# P_ytka.net
KiCad netlist of a schematic drawn in EAGLE
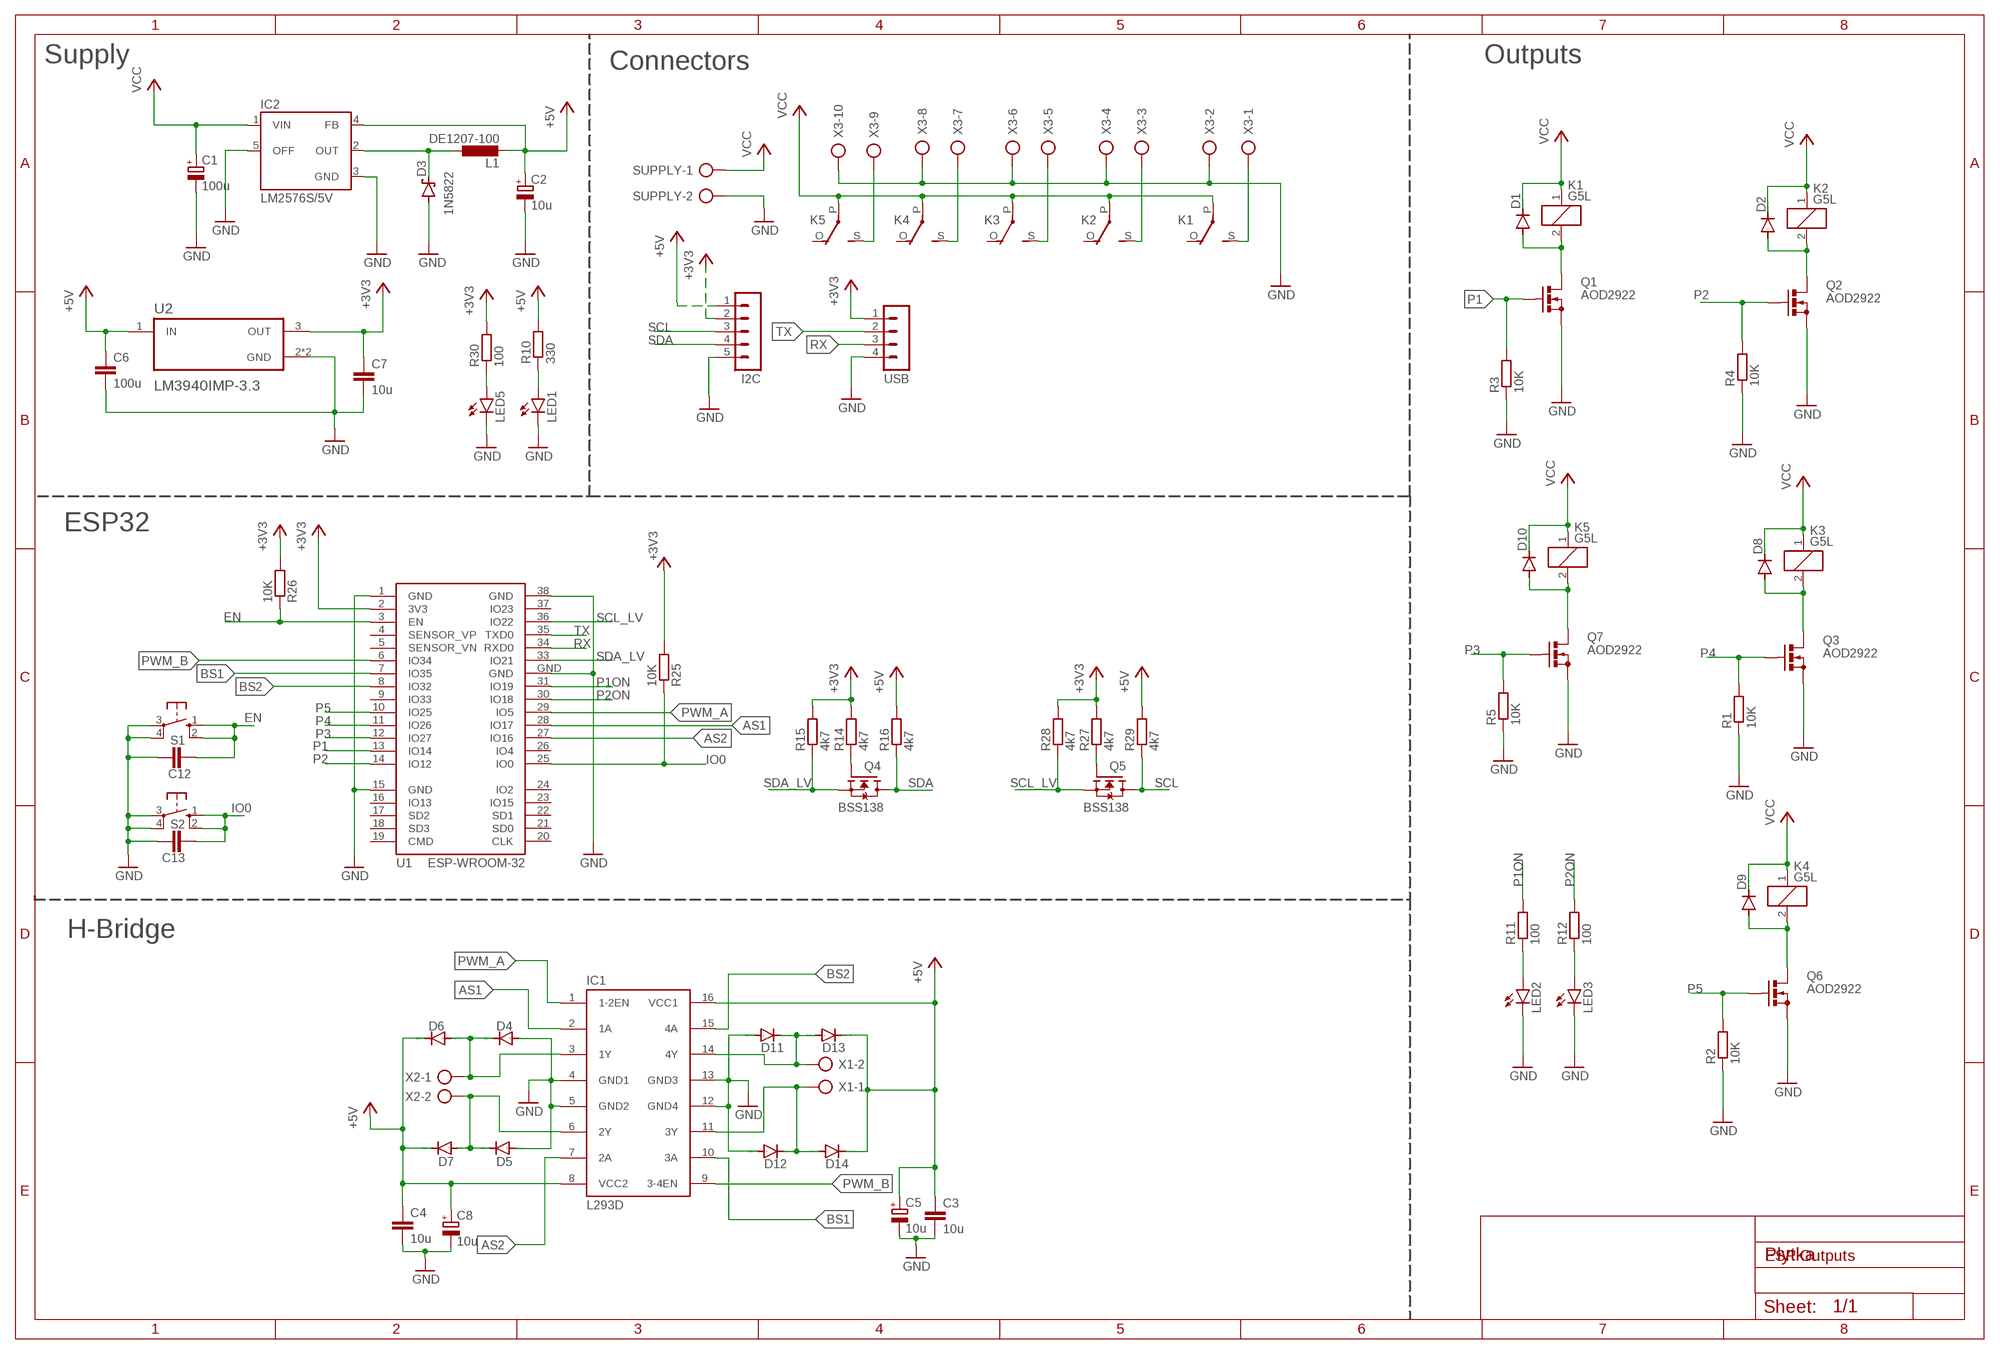
[diagram p0: schematic, sheet 1]

(export (version "E")
  (design (tool "Eeschema 10.0.6"))
  (components
    (comp (ref "C1")
      (value "100u")
      (footprint "eagle-import:E2,5-6")
      (libsource (lib "eagle-import") (part "CPOL-EUE2.5-6"))
    )
    (comp (ref "C2")
      (value "10u")
      (footprint "eagle-import:E3,5-8")
      (libsource (lib "eagle-import") (part "CPOL-EUE3.5-8"))
    )
    (comp (ref "C3")
      (value "10u")
      (footprint "eagle-import:C0805K")
      (libsource (lib "eagle-import") (part "resistor_348_C-EUC0805K"))
    )
    (comp (ref "C4")
      (value "10u")
      (footprint "eagle-import:C0805K")
      (libsource (lib "eagle-import") (part "resistor_348_C-EUC0805K"))
    )
    (comp (ref "C5")
      (value "10u")
      (footprint "eagle-import:E5-8,5")
      (libsource (lib "eagle-import") (part "resistor_348_CPOL-EUE5-8.5"))
    )
    (comp (ref "C6")
      (value "100u")
      (footprint "eagle-import:C0805K")
      (libsource (lib "eagle-import") (part "C-EUC0805K"))
    )
    (comp (ref "C7")
      (value "10u")
      (footprint "eagle-import:C0805K")
      (libsource (lib "eagle-import") (part "C-EUC0805K"))
    )
    (comp (ref "C8")
      (value "10u")
      (footprint "eagle-import:E5-8,5")
      (libsource (lib "eagle-import") (part "resistor_348_CPOL-EUE5-8.5"))
    )
    (comp (ref "C12")
      (value "C-EUC0805K")
      (footprint "eagle-import:C0805K")
      (libsource (lib "eagle-import") (part "C-EUC0805K"))
    )
    (comp (ref "C13")
      (value "C-EUC0805K")
      (footprint "eagle-import:C0805K")
      (libsource (lib "eagle-import") (part "C-EUC0805K"))
    )
    (comp (ref "D1")
      (value "DIODE-DO214AC")
      (footprint "eagle-import:DO214AC")
      (libsource (lib "eagle-import") (part "DIODE-DO214AC"))
    )
    (comp (ref "D2")
      (value "DIODE-DO214AC")
      (footprint "eagle-import:DO214AC")
      (libsource (lib "eagle-import") (part "DIODE-DO214AC"))
    )
    (comp (ref "D3")
      (value "1N5822")
      (footprint "eagle-import:C4111-15")
      (libsource (lib "eagle-import") (part "1N5908"))
    )
    (comp (ref "D4")
      (value "DIODE-DO214AC")
      (footprint "eagle-import:DO214AC")
      (libsource (lib "eagle-import") (part "DIODE-DO214AC"))
    )
    (comp (ref "D5")
      (value "DIODE-DO214AC")
      (footprint "eagle-import:DO214AC")
      (libsource (lib "eagle-import") (part "DIODE-DO214AC"))
    )
    (comp (ref "D6")
      (value "DIODE-DO214AC")
      (footprint "eagle-import:DO214AC")
      (libsource (lib "eagle-import") (part "DIODE-DO214AC"))
    )
    (comp (ref "D7")
      (value "DIODE-DO214AC")
      (footprint "eagle-import:DO214AC")
      (libsource (lib "eagle-import") (part "DIODE-DO214AC"))
    )
    (comp (ref "D8")
      (value "DIODE-DO214AC")
      (footprint "eagle-import:DO214AC")
      (libsource (lib "eagle-import") (part "DIODE-DO214AC"))
    )
    (comp (ref "D9")
      (value "DIODE-DO214AC")
      (footprint "eagle-import:DO214AC")
      (libsource (lib "eagle-import") (part "DIODE-DO214AC"))
    )
    (comp (ref "D10")
      (value "DIODE-DO214AC")
      (footprint "eagle-import:DO214AC")
      (libsource (lib "eagle-import") (part "DIODE-DO214AC"))
    )
    (comp (ref "D11")
      (value "DIODE-DO214AC")
      (footprint "eagle-import:DO214AC")
      (libsource (lib "eagle-import") (part "DIODE-DO214AC"))
    )
    (comp (ref "D12")
      (value "DIODE-DO214AC")
      (footprint "eagle-import:DO214AC")
      (libsource (lib "eagle-import") (part "DIODE-DO214AC"))
    )
    (comp (ref "D13")
      (value "DIODE-DO214AC")
      (footprint "eagle-import:DO214AC")
      (libsource (lib "eagle-import") (part "DIODE-DO214AC"))
    )
    (comp (ref "D14")
      (value "DIODE-DO214AC")
      (footprint "eagle-import:DO214AC")
      (libsource (lib "eagle-import") (part "DIODE-DO214AC"))
    )
    (comp (ref "I2C")
      (value "MA05-1")
      (footprint "eagle-import:MA05-1")
      (libsource (lib "eagle-import") (part "MA05-1"))
    )
    (comp (ref "IC1")
      (value "L293D")
      (footprint "eagle-import:DIL16")
      (libsource (lib "eagle-import") (part "L293D"))
    )
    (comp (ref "IC2")
      (value "LM2576S/5V")
      (footprint "eagle-import:TO220-5")
      (libsource (lib "eagle-import") (part "LM2576T"))
    )
    (comp (ref "K1")
      (value "G5L")
      (footprint "eagle-import:G5LE")
      (libsource (lib "eagle-import") (part "G5L"))
    )
    (comp (ref "K2")
      (value "G5L")
      (footprint "eagle-import:G5LE")
      (libsource (lib "eagle-import") (part "G5L"))
    )
    (comp (ref "K3")
      (value "G5L")
      (footprint "eagle-import:G5LE")
      (libsource (lib "eagle-import") (part "G5L"))
    )
    (comp (ref "K4")
      (value "G5L")
      (footprint "eagle-import:G5LE")
      (libsource (lib "eagle-import") (part "G5L"))
    )
    (comp (ref "K5")
      (value "G5L")
      (footprint "eagle-import:G5LE")
      (libsource (lib "eagle-import") (part "G5L"))
    )
    (comp (ref "L1")
      (value "DE1207-100")
      (footprint "eagle-import:DE1207")
      (libsource (lib "eagle-import") (part "DE1207-100"))
    )
    (comp (ref "LED1")
      (value "LEDSML0805")
      (footprint "eagle-import:SML0805")
      (libsource (lib "eagle-import") (part "LEDSML0805"))
    )
    (comp (ref "LED2")
      (value "LEDSML0805")
      (footprint "eagle-import:SML0805")
      (libsource (lib "eagle-import") (part "LEDSML0805"))
    )
    (comp (ref "LED3")
      (value "LEDSML0805")
      (footprint "eagle-import:SML0805")
      (libsource (lib "eagle-import") (part "LEDSML0805"))
    )
    (comp (ref "LED5")
      (value "LEDSML0805")
      (footprint "eagle-import:SML0805")
      (libsource (lib "eagle-import") (part "LEDSML0805"))
    )
    (comp (ref "Q1")
      (value "AOD2922")
      (footprint "eagle-import:TO252AA")
      (libsource (lib "eagle-import") (part "MOSFET_NIXTY8N65X2"))
    )
    (comp (ref "Q2")
      (value "AOD2922")
      (footprint "eagle-import:TO252AA")
      (libsource (lib "eagle-import") (part "MOSFET_NIXTY8N65X2"))
    )
    (comp (ref "Q3")
      (value "AOD2922")
      (footprint "eagle-import:TO252AA")
      (libsource (lib "eagle-import") (part "MOSFET_NIXTY8N65X2"))
    )
    (comp (ref "Q4")
      (value "BSS138")
      (footprint "eagle-import:SOT23")
      (fields (field (name "MF") "Fairchild"))
      (libsource (lib "eagle-import") (part "BSS138"))
    )
    (comp (ref "Q5")
      (value "BSS138")
      (footprint "eagle-import:SOT23")
      (fields (field (name "MF") "Fairchild"))
      (libsource (lib "eagle-import") (part "BSS138"))
    )
    (comp (ref "Q6")
      (value "AOD2922")
      (footprint "eagle-import:TO252AA")
      (libsource (lib "eagle-import") (part "MOSFET_NIXTY8N65X2"))
    )
    (comp (ref "Q7")
      (value "AOD2922")
      (footprint "eagle-import:TO252AA")
      (libsource (lib "eagle-import") (part "MOSFET_NIXTY8N65X2"))
    )
    (comp (ref "R1")
      (value "10K")
      (footprint "eagle-import:R0805")
      (libsource (lib "eagle-import") (part "R-EU_R0805"))
    )
    (comp (ref "R2")
      (value "10K")
      (footprint "eagle-import:R0805")
      (libsource (lib "eagle-import") (part "R-EU_R0805"))
    )
    (comp (ref "R3")
      (value "10K")
      (footprint "eagle-import:R0805")
      (libsource (lib "eagle-import") (part "R-EU_R0805"))
    )
    (comp (ref "R4")
      (value "10K")
      (footprint "eagle-import:R0805")
      (libsource (lib "eagle-import") (part "R-EU_R0805"))
    )
    (comp (ref "R5")
      (value "10K")
      (footprint "eagle-import:R0805")
      (libsource (lib "eagle-import") (part "R-EU_R0805"))
    )
    (comp (ref "R10")
      (value "330")
      (footprint "eagle-import:R0805")
      (libsource (lib "eagle-import") (part "R-EU_R0805"))
    )
    (comp (ref "R11")
      (value "100")
      (footprint "eagle-import:R0805")
      (libsource (lib "eagle-import") (part "R-EU_R0805"))
    )
    (comp (ref "R12")
      (value "100")
      (footprint "eagle-import:R0805")
      (libsource (lib "eagle-import") (part "R-EU_R0805"))
    )
    (comp (ref "R14")
      (value "4k7")
      (footprint "eagle-import:R0805")
      (libsource (lib "eagle-import") (part "R-EU_R0805"))
    )
    (comp (ref "R15")
      (value "4k7")
      (footprint "eagle-import:R0805")
      (libsource (lib "eagle-import") (part "R-EU_R0805"))
    )
    (comp (ref "R16")
      (value "4k7")
      (footprint "eagle-import:R0805")
      (libsource (lib "eagle-import") (part "R-EU_R0805"))
    )
    (comp (ref "R25")
      (value "10K")
      (footprint "eagle-import:R0805")
      (libsource (lib "eagle-import") (part "R-EU_R0805"))
    )
    (comp (ref "R26")
      (value "10K")
      (footprint "eagle-import:R0805")
      (libsource (lib "eagle-import") (part "R-EU_R0805"))
    )
    (comp (ref "R27")
      (value "4k7")
      (footprint "eagle-import:R0805")
      (libsource (lib "eagle-import") (part "R-EU_R0805"))
    )
    (comp (ref "R28")
      (value "4k7")
      (footprint "eagle-import:R0805")
      (libsource (lib "eagle-import") (part "R-EU_R0805"))
    )
    (comp (ref "R29")
      (value "4k7")
      (footprint "eagle-import:R0805")
      (libsource (lib "eagle-import") (part "R-EU_R0805"))
    )
    (comp (ref "R30")
      (value "100")
      (footprint "eagle-import:R0805")
      (libsource (lib "eagle-import") (part "R-EU_R0805"))
    )
    (comp (ref "S1")
      (value "10-XX")
      (footprint "eagle-import:B3F-10XX")
      (fields (field (name "MPN") "B3F-1000"))
      (libsource (lib "eagle-import") (part "10-XX"))
    )
    (comp (ref "S2")
      (value "10-XX")
      (footprint "eagle-import:B3F-10XX")
      (fields (field (name "MPN") "B3F-1000"))
      (libsource (lib "eagle-import") (part "10-XX"))
    )
    (comp (ref "SUPPLY")
      (value "AK500/2-H")
      (footprint "eagle-import:AK500_2-H")
      (libsource (lib "eagle-import") (part "AK500/2-H"))
    )
    (comp (ref "U1")
      (value "ESP-WROOM-32")
      (footprint "eagle-import:ESP-WROOM-32")
      (libsource (lib "eagle-import") (part "ESP-WROOM-32"))
    )
    (comp (ref "U2")
      (value "LM3940IMP-3.3")
      (footprint "eagle-import:SOT230P700X180-4N")
      (fields (field (name "MF") "Texas Instruments"))
      (libsource (lib "eagle-import") (part "LM3940IMP-3.3"))
    )
    (comp (ref "USB")
      (value "MA04-1")
      (footprint "eagle-import:MA04-1")
      (libsource (lib "eagle-import") (part "MA04-1"))
    )
    (comp (ref "X1")
      (value "AK500/2")
      (footprint "eagle-import:AK500_2")
      (libsource (lib "eagle-import") (part "AK500/2"))
    )
    (comp (ref "X2")
      (value "AK500/2")
      (footprint "eagle-import:AK500_2")
      (libsource (lib "eagle-import") (part "AK500/2"))
    )
    (comp (ref "X3")
      (value "AK500/10")
      (footprint "eagle-import:AK500_10")
      (libsource (lib "eagle-import") (part "AK500/10"))
    )
  )
  (nets
    (net (code "1") (name "+3V3") (class "Default")
      (node (ref "C7") (pin "1") (pinfunction "1_1") (pintype "passive"))
      (node (ref "I2C") (pin "2") (pinfunction "2_2") (pintype "passive"))
      (node (ref "R14") (pin "2") (pinfunction "2_2") (pintype "passive"))
      (node (ref "R15") (pin "2") (pinfunction "2_2") (pintype "passive"))
      (node (ref "R25") (pin "2") (pinfunction "2_2") (pintype "passive"))
      (node (ref "R26") (pin "2") (pinfunction "2_2") (pintype "passive"))
      (node (ref "R27") (pin "2") (pinfunction "2_2") (pintype "passive"))
      (node (ref "R28") (pin "2") (pinfunction "2_2") (pintype "passive"))
      (node (ref "R30") (pin "2") (pinfunction "2_2") (pintype "passive"))
      (node (ref "U1") (pin "2") (pinfunction "3V3_2") (pintype "power_in"))
      (node (ref "U2") (pin "3") (pinfunction "OUT_3") (pintype "output"))
      (node (ref "USB") (pin "1") (pinfunction "1_1") (pintype "passive"))
    )
    (net (code "2") (name "+5V") (class "Default")
      (node (ref "C2") (pin "+") (pinfunction "+_+") (pintype "passive"))
      (node (ref "C3") (pin "1") (pinfunction "1_1") (pintype "passive"))
      (node (ref "C4") (pin "1") (pinfunction "1_1") (pintype "passive"))
      (node (ref "C5") (pin "+") (pinfunction "+_+") (pintype "passive"))
      (node (ref "C6") (pin "1") (pinfunction "1_1") (pintype "passive"))
      (node (ref "C8") (pin "+") (pinfunction "+_+") (pintype "passive"))
      (node (ref "D13") (pin "C") (pinfunction "C_C") (pintype "passive"))
      (node (ref "D14") (pin "C") (pinfunction "C_C") (pintype "passive"))
      (node (ref "D6") (pin "C") (pinfunction "C_C") (pintype "passive"))
      (node (ref "D7") (pin "C") (pinfunction "C_C") (pintype "passive"))
      (node (ref "I2C") (pin "1") (pinfunction "1_1") (pintype "passive"))
      (node (ref "IC1") (pin "16") (pinfunction "VCC1_16") (pintype "power_in"))
      (node (ref "IC1") (pin "8") (pinfunction "VCC2_8") (pintype "power_in"))
      (node (ref "IC2") (pin "4") (pinfunction "FB_4") (pintype "input"))
      (node (ref "L1") (pin "2") (pinfunction "2_2") (pintype "passive"))
      (node (ref "R10") (pin "2") (pinfunction "2_2") (pintype "passive"))
      (node (ref "R16") (pin "2") (pinfunction "2_2") (pintype "passive"))
      (node (ref "R29") (pin "2") (pinfunction "2_2") (pintype "passive"))
      (node (ref "U2") (pin "1") (pinfunction "IN_1") (pintype "input"))
    )
    (net (code "3") (name "/EN") (class "Default")
      (node (ref "C12") (pin "2") (pinfunction "2_2") (pintype "passive"))
      (node (ref "R26") (pin "1") (pinfunction "1_1") (pintype "passive"))
      (node (ref "S1") (pin "1") (pinfunction "S_1") (pintype "passive"))
      (node (ref "S1") (pin "2") (pinfunction "S1_2") (pintype "passive"))
      (node (ref "U1") (pin "3") (pinfunction "EN_3") (pintype "input"))
    )
    (net (code "4") (name "/IO0") (class "Default")
      (node (ref "C13") (pin "2") (pinfunction "2_2") (pintype "passive"))
      (node (ref "R25") (pin "1") (pinfunction "1_1") (pintype "passive"))
      (node (ref "S2") (pin "1") (pinfunction "S_1") (pintype "passive"))
      (node (ref "S2") (pin "2") (pinfunction "S1_2") (pintype "passive"))
      (node (ref "U1") (pin "25") (pinfunction "IO0_25") (pintype "bidirectional"))
    )
    (net (code "5") (name "/P1ON") (class "Default")
      (node (ref "R11") (pin "2") (pinfunction "2_2") (pintype "passive"))
      (node (ref "U1") (pin "31") (pinfunction "IO19_31") (pintype "bidirectional"))
    )
    (net (code "6") (name "/P2") (class "Default")
      (node (ref "Q2") (pin "1") (pinfunction "G_1") (pintype "passive"))
      (node (ref "R4") (pin "2") (pinfunction "2_2") (pintype "passive"))
      (node (ref "U1") (pin "14") (pinfunction "IO12_14") (pintype "bidirectional"))
    )
    (net (code "7") (name "/P2ON") (class "Default")
      (node (ref "R12") (pin "2") (pinfunction "2_2") (pintype "passive"))
      (node (ref "U1") (pin "30") (pinfunction "IO18_30") (pintype "bidirectional"))
    )
    (net (code "8") (name "/P3") (class "Default")
      (node (ref "Q7") (pin "1") (pinfunction "G_1") (pintype "passive"))
      (node (ref "R5") (pin "2") (pinfunction "2_2") (pintype "passive"))
      (node (ref "U1") (pin "12") (pinfunction "IO27_12") (pintype "bidirectional"))
    )
    (net (code "9") (name "/P4") (class "Default")
      (node (ref "Q3") (pin "1") (pinfunction "G_1") (pintype "passive"))
      (node (ref "R1") (pin "2") (pinfunction "2_2") (pintype "passive"))
      (node (ref "U1") (pin "11") (pinfunction "IO26_11") (pintype "bidirectional"))
    )
    (net (code "10") (name "/P5") (class "Default")
      (node (ref "Q6") (pin "1") (pinfunction "G_1") (pintype "passive"))
      (node (ref "R2") (pin "2") (pinfunction "2_2") (pintype "passive"))
      (node (ref "U1") (pin "10") (pinfunction "IO25_10") (pintype "bidirectional"))
    )
    (net (code "11") (name "/SCL") (class "Default")
      (node (ref "I2C") (pin "3") (pinfunction "3_3") (pintype "passive"))
      (node (ref "Q5") (pin "3") (pinfunction "D_3") (pintype "passive"))
      (node (ref "R29") (pin "1") (pinfunction "1_1") (pintype "passive"))
    )
    (net (code "12") (name "/SCL_LV") (class "Default")
      (node (ref "Q5") (pin "2") (pinfunction "S_2") (pintype "passive"))
      (node (ref "R28") (pin "1") (pinfunction "1_1") (pintype "passive"))
      (node (ref "U1") (pin "36") (pinfunction "IO22_36") (pintype "bidirectional"))
    )
    (net (code "13") (name "/SDA") (class "Default")
      (node (ref "I2C") (pin "4") (pinfunction "4_4") (pintype "passive"))
      (node (ref "Q4") (pin "3") (pinfunction "D_3") (pintype "passive"))
      (node (ref "R16") (pin "1") (pinfunction "1_1") (pintype "passive"))
    )
    (net (code "14") (name "/SDA_LV") (class "Default")
      (node (ref "Q4") (pin "2") (pinfunction "S_2") (pintype "passive"))
      (node (ref "R15") (pin "1") (pinfunction "1_1") (pintype "passive"))
      (node (ref "U1") (pin "33") (pinfunction "IO21_33") (pintype "bidirectional"))
    )
    (net (code "15") (name "AS1") (class "Default")
      (node (ref "IC1") (pin "2") (pinfunction "1A_2") (pintype "input"))
      (node (ref "U1") (pin "28") (pinfunction "IO17_28") (pintype "bidirectional"))
    )
    (net (code "16") (name "AS2") (class "Default")
      (node (ref "IC1") (pin "7") (pinfunction "2A_7") (pintype "input"))
      (node (ref "U1") (pin "27") (pinfunction "IO16_27") (pintype "bidirectional"))
    )
    (net (code "17") (name "BS1") (class "Default")
      (node (ref "IC1") (pin "10") (pinfunction "3A_10") (pintype "input"))
      (node (ref "U1") (pin "7") (pinfunction "IO35_7") (pintype "bidirectional"))
    )
    (net (code "18") (name "BS2") (class "Default")
      (node (ref "IC1") (pin "15") (pinfunction "4A_15") (pintype "input"))
      (node (ref "U1") (pin "8") (pinfunction "IO32_8") (pintype "bidirectional"))
    )
    (net (code "19") (name "GND") (class "Default")
      (node (ref "C1") (pin "-") (pinfunction "-_-") (pintype "passive"))
      (node (ref "C12") (pin "1") (pinfunction "1_1") (pintype "passive"))
      (node (ref "C13") (pin "1") (pinfunction "1_1") (pintype "passive"))
      (node (ref "C2") (pin "-") (pinfunction "-_-") (pintype "passive"))
      (node (ref "C3") (pin "2") (pinfunction "2_2") (pintype "passive"))
      (node (ref "C4") (pin "2") (pinfunction "2_2") (pintype "passive"))
      (node (ref "C5") (pin "-") (pinfunction "-_-") (pintype "passive"))
      (node (ref "C6") (pin "2") (pinfunction "2_2") (pintype "passive"))
      (node (ref "C7") (pin "2") (pinfunction "2_2") (pintype "passive"))
      (node (ref "C8") (pin "-") (pinfunction "-_-") (pintype "passive"))
      (node (ref "D11") (pin "A") (pinfunction "A_A") (pintype "passive"))
      (node (ref "D12") (pin "A") (pinfunction "A_A") (pintype "passive"))
      (node (ref "D3") (pin "A") (pinfunction "A_A") (pintype "passive"))
      (node (ref "D4") (pin "A") (pinfunction "A_A") (pintype "passive"))
      (node (ref "D5") (pin "A") (pinfunction "A_A") (pintype "passive"))
      (node (ref "I2C") (pin "5") (pinfunction "5_5") (pintype "passive"))
      (node (ref "IC1") (pin "12") (pinfunction "GND4_12") (pintype "power_in"))
      (node (ref "IC1") (pin "13") (pinfunction "GND3_13") (pintype "power_in"))
      (node (ref "IC1") (pin "4") (pinfunction "GND1_4") (pintype "power_in"))
      (node (ref "IC1") (pin "5") (pinfunction "GND2_5") (pintype "power_in"))
      (node (ref "IC2") (pin "3") (pinfunction "GND_3") (pintype "power_in"))
      (node (ref "IC2") (pin "5") (pinfunction "OFF_5") (pintype "input"))
      (node (ref "LED1") (pin "C") (pinfunction "C_C") (pintype "passive"))
      (node (ref "LED2") (pin "C") (pinfunction "C_C") (pintype "passive"))
      (node (ref "LED3") (pin "C") (pinfunction "C_C") (pintype "passive"))
      (node (ref "LED5") (pin "C") (pinfunction "C_C") (pintype "passive"))
      (node (ref "Q1") (pin "2") (pinfunction "S_2") (pintype "passive"))
      (node (ref "Q2") (pin "2") (pinfunction "S_2") (pintype "passive"))
      (node (ref "Q3") (pin "2") (pinfunction "S_2") (pintype "passive"))
      (node (ref "Q6") (pin "2") (pinfunction "S_2") (pintype "passive"))
      (node (ref "Q7") (pin "2") (pinfunction "S_2") (pintype "passive"))
      (node (ref "R1") (pin "1") (pinfunction "1_1") (pintype "passive"))
      (node (ref "R2") (pin "1") (pinfunction "1_1") (pintype "passive"))
      (node (ref "R3") (pin "1") (pinfunction "1_1") (pintype "passive"))
      (node (ref "R4") (pin "1") (pinfunction "1_1") (pintype "passive"))
      (node (ref "R5") (pin "1") (pinfunction "1_1") (pintype "passive"))
      (node (ref "S1") (pin "3") (pinfunction "P_3") (pintype "passive"))
      (node (ref "S1") (pin "4") (pinfunction "P1_4") (pintype "passive"))
      (node (ref "S2") (pin "3") (pinfunction "P_3") (pintype "passive"))
      (node (ref "S2") (pin "4") (pinfunction "P1_4") (pintype "passive"))
      (node (ref "SUPPLY") (pin "2") (pinfunction "KL_2") (pintype "passive"))
      (node (ref "U1") (pin "1") (pinfunction "GND_1") (pintype "power_in"))
      (node (ref "U1") (pin "15") (pinfunction "GND_15") (pintype "power_in"))
      (node (ref "U1") (pin "38") (pinfunction "GND_38") (pintype "power_in"))
      (node (ref "U1") (pin "GND") (pinfunction "GND_GND") (pintype "power_in"))
      (node (ref "U2") (pin "2") (pinfunction "GND_2") (pintype "power_in"))
      (node (ref "U2") (pin "4") (pinfunction "GND_4") (pintype "power_in"))
      (node (ref "USB") (pin "4") (pinfunction "4_4") (pintype "passive"))
      (node (ref "X3") (pin "10") (pinfunction "KL_10") (pintype "passive"))
      (node (ref "X3") (pin "2") (pinfunction "KL_2") (pintype "passive"))
      (node (ref "X3") (pin "4") (pinfunction "KL_4") (pintype "passive"))
      (node (ref "X3") (pin "6") (pinfunction "KL_6") (pintype "passive"))
      (node (ref "X3") (pin "8") (pinfunction "KL_8") (pintype "passive"))
    )
    (net (code "20") (name "Net-(IC1-1Y)") (class "Default")
      (node (ref "D4") (pin "C") (pinfunction "C_C") (pintype "passive"))
      (node (ref "D6") (pin "A") (pinfunction "A_A") (pintype "passive"))
      (node (ref "IC1") (pin "3") (pinfunction "1Y_3") (pintype "output"))
      (node (ref "X2") (pin "1") (pinfunction "KL_1") (pintype "passive"))
    )
    (net (code "21") (name "Net-(IC1-2Y)") (class "Default")
      (node (ref "D5") (pin "C") (pinfunction "C_C") (pintype "passive"))
      (node (ref "D7") (pin "A") (pinfunction "A_A") (pintype "passive"))
      (node (ref "IC1") (pin "6") (pinfunction "2Y_6") (pintype "output"))
      (node (ref "X2") (pin "2") (pinfunction "KL_2") (pintype "passive"))
    )
    (net (code "22") (name "Net-(IC1-3Y)") (class "Default")
      (node (ref "D12") (pin "C") (pinfunction "C_C") (pintype "passive"))
      (node (ref "D14") (pin "A") (pinfunction "A_A") (pintype "passive"))
      (node (ref "IC1") (pin "11") (pinfunction "3Y_11") (pintype "output"))
      (node (ref "X1") (pin "1") (pinfunction "KL_1") (pintype "passive"))
    )
    (net (code "23") (name "Net-(IC1-4Y)") (class "Default")
      (node (ref "D11") (pin "C") (pinfunction "C_C") (pintype "passive"))
      (node (ref "D13") (pin "A") (pinfunction "A_A") (pintype "passive"))
      (node (ref "IC1") (pin "14") (pinfunction "4Y_14") (pintype "output"))
      (node (ref "X1") (pin "2") (pinfunction "KL_2") (pintype "passive"))
    )
    (net (code "24") (name "Net-(IC2-OUT)") (class "Default")
      (node (ref "D3") (pin "C") (pinfunction "C_C") (pintype "passive"))
      (node (ref "IC2") (pin "2") (pinfunction "OUT_2") (pintype "output"))
      (node (ref "L1") (pin "1") (pinfunction "1_1") (pintype "passive"))
    )
    (net (code "25") (name "Net-(LED1-PadA)") (class "Default")
      (node (ref "LED1") (pin "A") (pinfunction "A_A") (pintype "passive"))
      (node (ref "R10") (pin "1") (pinfunction "1_1") (pintype "passive"))
    )
    (net (code "26") (name "Net-(LED2-PadA)") (class "Default")
      (node (ref "LED2") (pin "A") (pinfunction "A_A") (pintype "passive"))
      (node (ref "R11") (pin "1") (pinfunction "1_1") (pintype "passive"))
    )
    (net (code "27") (name "Net-(LED3-PadA)") (class "Default")
      (node (ref "LED3") (pin "A") (pinfunction "A_A") (pintype "passive"))
      (node (ref "R12") (pin "1") (pinfunction "1_1") (pintype "passive"))
    )
    (net (code "28") (name "Net-(LED5-PadA)") (class "Default")
      (node (ref "LED5") (pin "A") (pinfunction "A_A") (pintype "passive"))
      (node (ref "R30") (pin "1") (pinfunction "1_1") (pintype "passive"))
    )
    (net (code "29") (name "Net-(Q1-D)") (class "Default")
      (node (ref "D1") (pin "A") (pinfunction "A_A") (pintype "passive"))
      (node (ref "K1") (pin "2") (pinfunction "2_2") (pintype "passive"))
      (node (ref "Q1") (pin "3") (pinfunction "D_3") (pintype "passive"))
    )
    (net (code "30") (name "Net-(Q2-D)") (class "Default")
      (node (ref "D2") (pin "A") (pinfunction "A_A") (pintype "passive"))
      (node (ref "K2") (pin "2") (pinfunction "2_2") (pintype "passive"))
      (node (ref "Q2") (pin "3") (pinfunction "D_3") (pintype "passive"))
    )
    (net (code "31") (name "Net-(Q3-D)") (class "Default")
      (node (ref "D8") (pin "A") (pinfunction "A_A") (pintype "passive"))
      (node (ref "K3") (pin "2") (pinfunction "2_2") (pintype "passive"))
      (node (ref "Q3") (pin "3") (pinfunction "D_3") (pintype "passive"))
    )
    (net (code "32") (name "Net-(Q4-G)") (class "Default")
      (node (ref "Q4") (pin "1") (pinfunction "G_1") (pintype "passive"))
      (node (ref "R14") (pin "1") (pinfunction "1_1") (pintype "passive"))
    )
    (net (code "33") (name "Net-(Q5-G)") (class "Default")
      (node (ref "Q5") (pin "1") (pinfunction "G_1") (pintype "passive"))
      (node (ref "R27") (pin "1") (pinfunction "1_1") (pintype "passive"))
    )
    (net (code "34") (name "Net-(Q6-D)") (class "Default")
      (node (ref "D9") (pin "A") (pinfunction "A_A") (pintype "passive"))
      (node (ref "K4") (pin "2") (pinfunction "2_2") (pintype "passive"))
      (node (ref "Q6") (pin "3") (pinfunction "D_3") (pintype "passive"))
    )
    (net (code "35") (name "Net-(Q7-D)") (class "Default")
      (node (ref "D10") (pin "A") (pinfunction "A_A") (pintype "passive"))
      (node (ref "K5") (pin "2") (pinfunction "2_2") (pintype "passive"))
      (node (ref "Q7") (pin "3") (pinfunction "D_3") (pintype "passive"))
    )
    (net (code "36") (name "Net-(X3A-KL)") (class "Default")
      (node (ref "K1") (pin "S") (pinfunction "S_S") (pintype "passive"))
      (node (ref "X3") (pin "1") (pinfunction "KL_1") (pintype "passive"))
    )
    (net (code "37") (name "Net-(X3D-KL)") (class "Default")
      (node (ref "K2") (pin "S") (pinfunction "S_S") (pintype "passive"))
      (node (ref "X3") (pin "3") (pinfunction "KL_3") (pintype "passive"))
    )
    (net (code "38") (name "Net-(X3F-KL)") (class "Default")
      (node (ref "K3") (pin "S") (pinfunction "S_S") (pintype "passive"))
      (node (ref "X3") (pin "5") (pinfunction "KL_5") (pintype "passive"))
    )
    (net (code "39") (name "Net-(X3H-KL)") (class "Default")
      (node (ref "K4") (pin "S") (pinfunction "S_S") (pintype "passive"))
      (node (ref "X3") (pin "7") (pinfunction "KL_7") (pintype "passive"))
    )
    (net (code "40") (name "Net-(X3J-KL)") (class "Default")
      (node (ref "K5") (pin "S") (pinfunction "S_S") (pintype "passive"))
      (node (ref "X3") (pin "9") (pinfunction "KL_9") (pintype "passive"))
    )
    (net (code "41") (name "P1") (class "Default")
      (node (ref "Q1") (pin "1") (pinfunction "G_1") (pintype "passive"))
      (node (ref "R3") (pin "2") (pinfunction "2_2") (pintype "passive"))
      (node (ref "U1") (pin "13") (pinfunction "IO14_13") (pintype "bidirectional"))
    )
    (net (code "42") (name "PWM_A") (class "Default")
      (node (ref "IC1") (pin "1") (pinfunction "1-2EN_1") (pintype "input"))
      (node (ref "U1") (pin "29") (pinfunction "IO5_29") (pintype "bidirectional"))
    )
    (net (code "43") (name "PWM_B") (class "Default")
      (node (ref "IC1") (pin "9") (pinfunction "3-4EN_9") (pintype "input"))
      (node (ref "U1") (pin "6") (pinfunction "IO34_6") (pintype "bidirectional"))
    )
    (net (code "44") (name "RX") (class "Default")
      (node (ref "U1") (pin "34") (pinfunction "RXD0_34") (pintype "bidirectional"))
      (node (ref "USB") (pin "3") (pinfunction "3_3") (pintype "passive"))
    )
    (net (code "45") (name "TX") (class "Default")
      (node (ref "U1") (pin "35") (pinfunction "TXD0_35") (pintype "bidirectional"))
      (node (ref "USB") (pin "2") (pinfunction "2_2") (pintype "passive"))
    )
    (net (code "46") (name "VCC") (class "Default")
      (node (ref "C1") (pin "+") (pinfunction "+_+") (pintype "passive"))
      (node (ref "D1") (pin "C") (pinfunction "C_C") (pintype "passive"))
      (node (ref "D10") (pin "C") (pinfunction "C_C") (pintype "passive"))
      (node (ref "D2") (pin "C") (pinfunction "C_C") (pintype "passive"))
      (node (ref "D8") (pin "C") (pinfunction "C_C") (pintype "passive"))
      (node (ref "D9") (pin "C") (pinfunction "C_C") (pintype "passive"))
      (node (ref "IC2") (pin "1") (pinfunction "VIN_1") (pintype "power_in"))
      (node (ref "K1") (pin "1") (pinfunction "1_1") (pintype "passive"))
      (node (ref "K1") (pin "P") (pinfunction "P_P") (pintype "passive"))
      (node (ref "K2") (pin "1") (pinfunction "1_1") (pintype "passive"))
      (node (ref "K2") (pin "P") (pinfunction "P_P") (pintype "passive"))
      (node (ref "K3") (pin "1") (pinfunction "1_1") (pintype "passive"))
      (node (ref "K3") (pin "P") (pinfunction "P_P") (pintype "passive"))
      (node (ref "K4") (pin "1") (pinfunction "1_1") (pintype "passive"))
      (node (ref "K4") (pin "P") (pinfunction "P_P") (pintype "passive"))
      (node (ref "K5") (pin "1") (pinfunction "1_1") (pintype "passive"))
      (node (ref "K5") (pin "P") (pinfunction "P_P") (pintype "passive"))
      (node (ref "SUPPLY") (pin "1") (pinfunction "KL_1") (pintype "passive"))
    )
    (net (code "47") (name "unconnected-(K1-PadO)") (class "Default")
      (node (ref "K1") (pin "O") (pinfunction "O_O") (pintype "passive"))
    )
    (net (code "48") (name "unconnected-(K2-PadO)") (class "Default")
      (node (ref "K2") (pin "O") (pinfunction "O_O") (pintype "passive"))
    )
    (net (code "49") (name "unconnected-(K3-PadO)") (class "Default")
      (node (ref "K3") (pin "O") (pinfunction "O_O") (pintype "passive"))
    )
    (net (code "50") (name "unconnected-(K4-PadO)") (class "Default")
      (node (ref "K4") (pin "O") (pinfunction "O_O") (pintype "passive"))
    )
    (net (code "51") (name "unconnected-(K5-PadO)") (class "Default")
      (node (ref "K5") (pin "O") (pinfunction "O_O") (pintype "passive"))
    )
    (net (code "52") (name "unconnected-(U1-CLK-Pad20)") (class "Default")
      (node (ref "U1") (pin "20") (pinfunction "CLK_20") (pintype "bidirectional"))
    )
    (net (code "53") (name "unconnected-(U1-CMD-Pad19)") (class "Default")
      (node (ref "U1") (pin "19") (pinfunction "CMD_19") (pintype "bidirectional"))
    )
    (net (code "54") (name "unconnected-(U1-IO2-Pad24)") (class "Default")
      (node (ref "U1") (pin "24") (pinfunction "IO2_24") (pintype "bidirectional"))
    )
    (net (code "55") (name "unconnected-(U1-IO4-Pad26)") (class "Default")
      (node (ref "U1") (pin "26") (pinfunction "IO4_26") (pintype "bidirectional"))
    )
    (net (code "56") (name "unconnected-(U1-IO13-Pad16)") (class "Default")
      (node (ref "U1") (pin "16") (pinfunction "IO13_16") (pintype "bidirectional"))
    )
    (net (code "57") (name "unconnected-(U1-IO15-Pad23)") (class "Default")
      (node (ref "U1") (pin "23") (pinfunction "IO15_23") (pintype "bidirectional"))
    )
    (net (code "58") (name "unconnected-(U1-IO23-Pad37)") (class "Default")
      (node (ref "U1") (pin "37") (pinfunction "IO23_37") (pintype "bidirectional"))
    )
    (net (code "59") (name "unconnected-(U1-IO33-Pad9)") (class "Default")
      (node (ref "U1") (pin "9") (pinfunction "IO33_9") (pintype "bidirectional"))
    )
    (net (code "60") (name "unconnected-(U1-SD0-Pad21)") (class "Default")
      (node (ref "U1") (pin "21") (pinfunction "SD0_21") (pintype "bidirectional"))
    )
    (net (code "61") (name "unconnected-(U1-SD1-Pad22)") (class "Default")
      (node (ref "U1") (pin "22") (pinfunction "SD1_22") (pintype "bidirectional"))
    )
    (net (code "62") (name "unconnected-(U1-SD2-Pad17)") (class "Default")
      (node (ref "U1") (pin "17") (pinfunction "SD2_17") (pintype "bidirectional"))
    )
    (net (code "63") (name "unconnected-(U1-SD3-Pad18)") (class "Default")
      (node (ref "U1") (pin "18") (pinfunction "SD3_18") (pintype "bidirectional"))
    )
    (net (code "64") (name "unconnected-(U1-SENSOR_VN-Pad5)") (class "Default")
      (node (ref "U1") (pin "5") (pinfunction "SENSOR_VN_5") (pintype "bidirectional"))
    )
    (net (code "65") (name "unconnected-(U1-SENSOR_VP-Pad4)") (class "Default")
      (node (ref "U1") (pin "4") (pinfunction "SENSOR_VP_4") (pintype "bidirectional"))
    )
  )
)
